# powerboard_v1.net
KiCad netlist of a schematic drawn in EAGLE
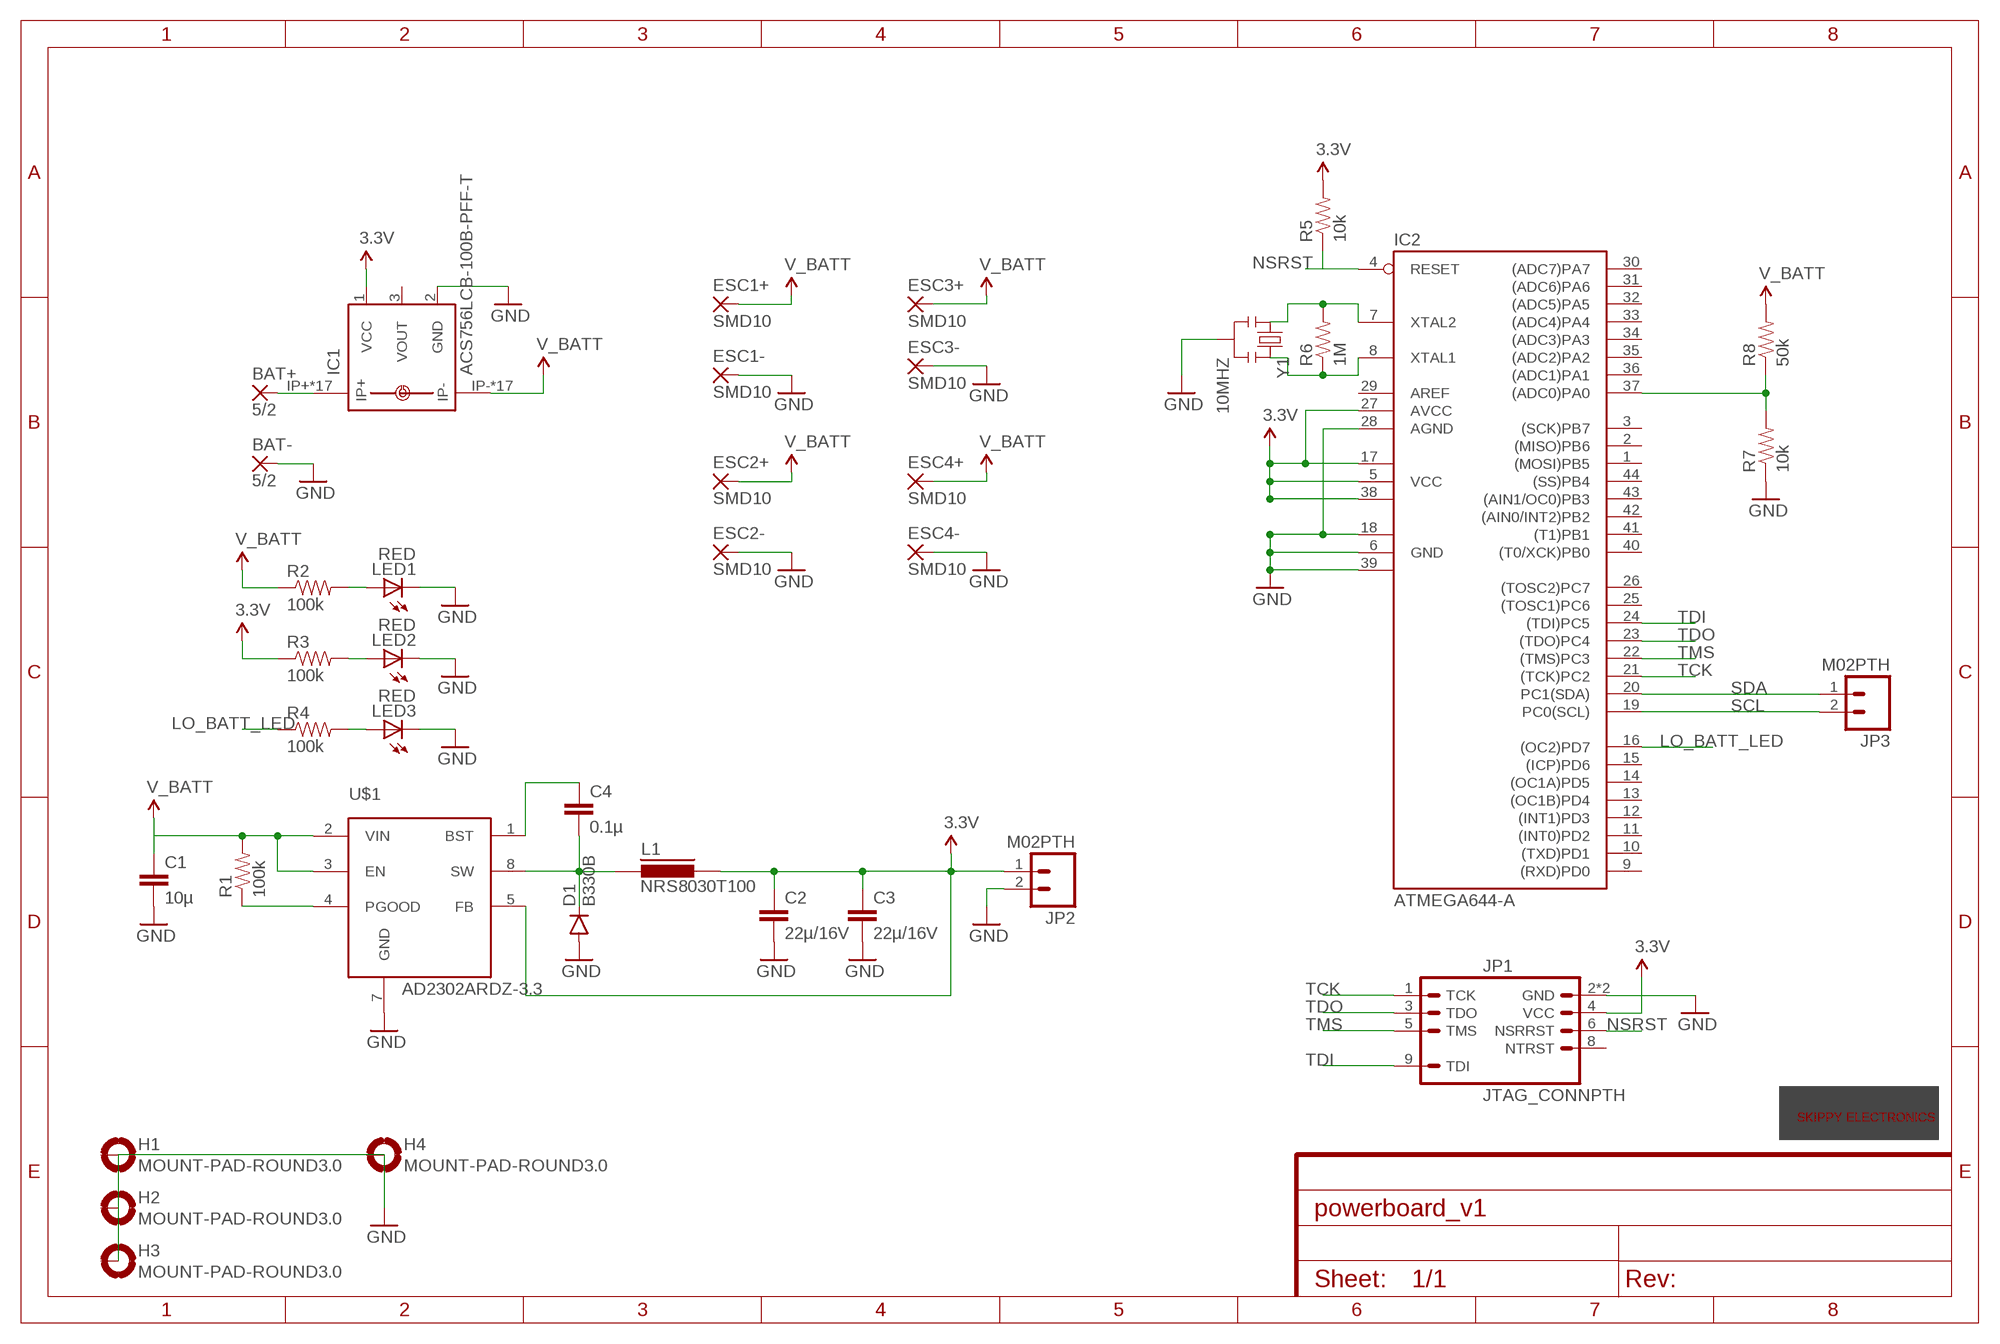
[diagram p0: schematic, sheet 1]

(export (version "E")
  (design (tool "Eeschema 10.0.6"))
  (components
    (comp (ref "BAT+")
      (value "5/2")
      (footprint "eagle-import:5_2")
      (libsource (lib "eagle-import") (part "5/2"))
    )
    (comp (ref "BAT-")
      (value "5/2")
      (footprint "eagle-import:5_2")
      (libsource (lib "eagle-import") (part "5/2"))
    )
    (comp (ref "C1")
      (value "10µ")
      (footprint "eagle-import:1206")
      (libsource (lib "eagle-import") (part "CAP1206"))
    )
    (comp (ref "C2")
      (value "22µ/16V")
      (footprint "eagle-import:1206")
      (libsource (lib "eagle-import") (part "CAP1206"))
    )
    (comp (ref "C3")
      (value "22µ/16V")
      (footprint "eagle-import:1206")
      (libsource (lib "eagle-import") (part "CAP1206"))
    )
    (comp (ref "C4")
      (value "0.1µ")
      (footprint "eagle-import:1206")
      (libsource (lib "eagle-import") (part "CAP1206"))
    )
    (comp (ref "D1")
      (value "B330B")
      (footprint "eagle-import:SMB-DIODE")
      (libsource (lib "eagle-import") (part "DIODESMB"))
    )
    (comp (ref "ESC1+")
      (value "SMD10")
      (footprint "eagle-import:SMD5.08-10.16")
      (libsource (lib "eagle-import") (part "SMD10"))
    )
    (comp (ref "ESC1-")
      (value "SMD10")
      (footprint "eagle-import:SMD5.08-10.16")
      (libsource (lib "eagle-import") (part "SMD10"))
    )
    (comp (ref "ESC2+")
      (value "SMD10")
      (footprint "eagle-import:SMD5.08-10.16")
      (libsource (lib "eagle-import") (part "SMD10"))
    )
    (comp (ref "ESC2-")
      (value "SMD10")
      (footprint "eagle-import:SMD5.08-10.16")
      (libsource (lib "eagle-import") (part "SMD10"))
    )
    (comp (ref "ESC3+")
      (value "SMD10")
      (footprint "eagle-import:SMD5.08-10.16")
      (libsource (lib "eagle-import") (part "SMD10"))
    )
    (comp (ref "ESC3-")
      (value "SMD10")
      (footprint "eagle-import:SMD5.08-10.16")
      (libsource (lib "eagle-import") (part "SMD10"))
    )
    (comp (ref "ESC4+")
      (value "SMD10")
      (footprint "eagle-import:SMD5.08-10.16")
      (libsource (lib "eagle-import") (part "SMD10"))
    )
    (comp (ref "ESC4-")
      (value "SMD10")
      (footprint "eagle-import:SMD5.08-10.16")
      (libsource (lib "eagle-import") (part "SMD10"))
    )
    (comp (ref "H1")
      (value "MOUNT-PAD-ROUND3.0")
      (footprint "eagle-import:3,0-PAD")
      (libsource (lib "eagle-import") (part "MOUNT-PAD-ROUND3.0"))
    )
    (comp (ref "H2")
      (value "MOUNT-PAD-ROUND3.0")
      (footprint "eagle-import:3,0-PAD")
      (libsource (lib "eagle-import") (part "MOUNT-PAD-ROUND3.0"))
    )
    (comp (ref "H3")
      (value "MOUNT-PAD-ROUND3.0")
      (footprint "eagle-import:3,0-PAD")
      (libsource (lib "eagle-import") (part "MOUNT-PAD-ROUND3.0"))
    )
    (comp (ref "H4")
      (value "MOUNT-PAD-ROUND3.0")
      (footprint "eagle-import:3,0-PAD")
      (libsource (lib "eagle-import") (part "MOUNT-PAD-ROUND3.0"))
    )
    (comp (ref "IC1")
      (value "ACS756LCB-100B-PFF-T")
      (footprint "eagle-import:CB-PFF")
      (fields (field (name "MPN") "ACS758LCB-100B-PFF-T"))
      (libsource (lib "eagle-import") (part "ACS756LCB-100B-PFF-T"))
    )
    (comp (ref "IC2")
      (value "ATMEGA644-A")
      (footprint "eagle-import:TQFP44")
      (libsource (lib "eagle-import") (part "ATMEGA644-A"))
    )
    (comp (ref "JP1")
      (value "JTAG_CONNPTH")
      (footprint "eagle-import:AVR_ICSP")
      (libsource (lib "eagle-import") (part "JTAG_CONNPTH"))
    )
    (comp (ref "JP2")
      (value "M02PTH")
      (footprint "eagle-import:1X02")
      (libsource (lib "eagle-import") (part "M02PTH"))
    )
    (comp (ref "JP3")
      (value "M02PTH")
      (footprint "eagle-import:1X02")
      (libsource (lib "eagle-import") (part "M02PTH"))
    )
    (comp (ref "L1")
      (value "NRS8030T100")
      (footprint "eagle-import:NRS8030")
      (libsource (lib "eagle-import") (part "NRS8030T100"))
    )
    (comp (ref "LED1")
      (value "RED")
      (footprint "eagle-import:LED_1206")
      (libsource (lib "eagle-import") (part "LED_E"))
    )
    (comp (ref "LED2")
      (value "RED")
      (footprint "eagle-import:LED_1206")
      (libsource (lib "eagle-import") (part "LED_E"))
    )
    (comp (ref "LED3")
      (value "RED")
      (footprint "eagle-import:LED_1206")
      (libsource (lib "eagle-import") (part "LED_E"))
    )
    (comp (ref "PLC1")
      (value "SKIPPY-PLC-10MMPLC")
      (footprint "eagle-import:SKIPPY-PLC-10MM")
      (libsource (lib "eagle-import") (part "SKIPPY-PLC-10MMPLC"))
    )
    (comp (ref "R1")
      (value "100k")
      (footprint "eagle-import:1206")
      (libsource (lib "eagle-import") (part "RESISTOR1206"))
    )
    (comp (ref "R2")
      (value "100k")
      (footprint "eagle-import:1206")
      (libsource (lib "eagle-import") (part "RESISTOR1206"))
    )
    (comp (ref "R3")
      (value "100k")
      (footprint "eagle-import:1206")
      (libsource (lib "eagle-import") (part "RESISTOR1206"))
    )
    (comp (ref "R4")
      (value "100k")
      (footprint "eagle-import:1206")
      (libsource (lib "eagle-import") (part "RESISTOR1206"))
    )
    (comp (ref "R5")
      (value "10k")
      (footprint "eagle-import:1206")
      (libsource (lib "eagle-import") (part "RESISTOR1206"))
    )
    (comp (ref "R6")
      (value "1M")
      (footprint "eagle-import:1206")
      (libsource (lib "eagle-import") (part "RESISTOR1206"))
    )
    (comp (ref "R7")
      (value "10k")
      (footprint "eagle-import:1206")
      (libsource (lib "eagle-import") (part "RESISTOR1206"))
    )
    (comp (ref "R8")
      (value "50k")
      (footprint "eagle-import:1206")
      (libsource (lib "eagle-import") (part "RESISTOR1206"))
    )
    (comp (ref "U$1")
      (value "AD2302ARDZ-3.3")
      (footprint "eagle-import:SO8")
      (libsource (lib "eagle-import") (part "AD2302ARDZ-3.3"))
    )
    (comp (ref "Y1")
      (value "10MHZ")
      (footprint "eagle-import:RESONATOR-SMD")
      (libsource (lib "eagle-import") (part "RESONATOR8MHZ"))
    )
  )
  (nets
    (net (code "1") (name "/LO_BATT_LED") (class "Default")
      (node (ref "IC2") (pin "16") (pinfunction "(OC2)PD7_16") (pintype "bidirectional"))
      (node (ref "R4") (pin "1") (pinfunction "1_1") (pintype "passive"))
    )
    (net (code "2") (name "/NSRST") (class "Default")
      (node (ref "IC2") (pin "4") (pinfunction "RESET_4") (pintype "input"))
      (node (ref "JP1") (pin "6") (pinfunction "NSRRST_6") (pintype "passive"))
      (node (ref "R5") (pin "1") (pinfunction "1_1") (pintype "passive"))
    )
    (net (code "3") (name "/SCL") (class "Default")
      (node (ref "IC2") (pin "19") (pinfunction "PC0(SCL)_19") (pintype "bidirectional"))
      (node (ref "JP3") (pin "2") (pinfunction "2_2") (pintype "passive"))
    )
    (net (code "4") (name "/SDA") (class "Default")
      (node (ref "IC2") (pin "20") (pinfunction "PC1(SDA)_20") (pintype "bidirectional"))
      (node (ref "JP3") (pin "1") (pinfunction "1_1") (pintype "passive"))
    )
    (net (code "5") (name "/TCK") (class "Default")
      (node (ref "IC2") (pin "21") (pinfunction "(TCK)PC2_21") (pintype "bidirectional"))
      (node (ref "JP1") (pin "1") (pinfunction "TCK_1") (pintype "passive"))
    )
    (net (code "6") (name "/TDI") (class "Default")
      (node (ref "IC2") (pin "24") (pinfunction "(TDI)PC5_24") (pintype "bidirectional"))
      (node (ref "JP1") (pin "9") (pinfunction "TDI_9") (pintype "passive"))
    )
    (net (code "7") (name "/TDO") (class "Default")
      (node (ref "IC2") (pin "23") (pinfunction "(TDO)PC4_23") (pintype "bidirectional"))
      (node (ref "JP1") (pin "3") (pinfunction "TDO_3") (pintype "passive"))
    )
    (net (code "8") (name "/TMS") (class "Default")
      (node (ref "IC2") (pin "22") (pinfunction "(TMS)PC3_22") (pintype "bidirectional"))
      (node (ref "JP1") (pin "5") (pinfunction "TMS_5") (pintype "passive"))
    )
    (net (code "9") (name "3.3V") (class "Default")
      (node (ref "C2") (pin "1") (pinfunction "1_1") (pintype "passive"))
      (node (ref "C3") (pin "1") (pinfunction "1_1") (pintype "passive"))
      (node (ref "IC1") (pin "1") (pinfunction "VCC_1") (pintype "power_in"))
      (node (ref "IC2") (pin "17") (pinfunction "VCC1_17") (pintype "power_in"))
      (node (ref "IC2") (pin "27") (pinfunction "AVCC_27") (pintype "power_in"))
      (node (ref "IC2") (pin "38") (pinfunction "VCC2_38") (pintype "power_in"))
      (node (ref "IC2") (pin "5") (pinfunction "VCC_5") (pintype "power_in"))
      (node (ref "JP1") (pin "4") (pinfunction "VCC_4") (pintype "passive"))
      (node (ref "JP2") (pin "1") (pinfunction "1_1") (pintype "passive"))
      (node (ref "L1") (pin "P$2") (pinfunction "2_P$2") (pintype "passive"))
      (node (ref "R3") (pin "1") (pinfunction "1_1") (pintype "passive"))
      (node (ref "R5") (pin "2") (pinfunction "2_2") (pintype "passive"))
      (node (ref "U$1") (pin "5") (pinfunction "FB_5") (pintype "input"))
    )
    (net (code "10") (name "GND") (class "Default")
      (node (ref "BAT-") (pin "P$1") (pinfunction "P_P$1") (pintype "passive"))
      (node (ref "C1") (pin "2") (pinfunction "2_2") (pintype "passive"))
      (node (ref "C2") (pin "2") (pinfunction "2_2") (pintype "passive"))
      (node (ref "C3") (pin "2") (pinfunction "2_2") (pintype "passive"))
      (node (ref "D1") (pin "A") (pinfunction "A_A") (pintype "passive"))
      (node (ref "ESC1-") (pin "P$1") (pinfunction "P_P$1") (pintype "passive"))
      (node (ref "ESC1-") (pin "P$2") (pinfunction "P_P$2") (pintype "passive"))
      (node (ref "ESC2-") (pin "P$1") (pinfunction "P_P$1") (pintype "passive"))
      (node (ref "ESC2-") (pin "P$2") (pinfunction "P_P$2") (pintype "passive"))
      (node (ref "ESC3-") (pin "P$1") (pinfunction "P_P$1") (pintype "passive"))
      (node (ref "ESC3-") (pin "P$2") (pinfunction "P_P$2") (pintype "passive"))
      (node (ref "ESC4-") (pin "P$1") (pinfunction "P_P$1") (pintype "passive"))
      (node (ref "ESC4-") (pin "P$2") (pinfunction "P_P$2") (pintype "passive"))
      (node (ref "IC1") (pin "2") (pinfunction "GND_2") (pintype "power_in"))
      (node (ref "IC2") (pin "18") (pinfunction "GND1_18") (pintype "power_in"))
      (node (ref "IC2") (pin "28") (pinfunction "AGND_28") (pintype "power_in"))
      (node (ref "IC2") (pin "39") (pinfunction "GND2_39") (pintype "power_in"))
      (node (ref "IC2") (pin "6") (pinfunction "GND_6") (pintype "power_in"))
      (node (ref "JP1") (pin "10") (pinfunction "GND_10") (pintype "power_in"))
      (node (ref "JP1") (pin "2") (pinfunction "GND_2") (pintype "power_in"))
      (node (ref "JP2") (pin "2") (pinfunction "2_2") (pintype "passive"))
      (node (ref "LED1") (pin "C") (pinfunction "C_C") (pintype "passive"))
      (node (ref "LED2") (pin "C") (pinfunction "C_C") (pintype "passive"))
      (node (ref "LED3") (pin "C") (pinfunction "C_C") (pintype "passive"))
      (node (ref "R7") (pin "1") (pinfunction "1_1") (pintype "passive"))
      (node (ref "U$1") (pin "7") (pinfunction "GND_7") (pintype "power_in"))
      (node (ref "Y1") (pin "2") (pinfunction "2_2") (pintype "passive"))
    )
    (net (code "11") (name "Net-(BAT+-P)") (class "Default")
      (node (ref "BAT+") (pin "P$1") (pinfunction "P_P$1") (pintype "passive"))
      (node (ref "IC1") (pin "IP+") (pinfunction "IP+_IP+") (pintype "passive"))
      (node (ref "IC1") (pin "IP+@10") (pinfunction "IP+_IP+@10") (pintype "passive"))
      (node (ref "IC1") (pin "IP+@11") (pinfunction "IP+_IP+@11") (pintype "passive"))
      (node (ref "IC1") (pin "IP+@12") (pinfunction "IP+_IP+@12") (pintype "passive"))
      (node (ref "IC1") (pin "IP+@13") (pinfunction "IP+_IP+@13") (pintype "passive"))
      (node (ref "IC1") (pin "IP+@14") (pinfunction "IP+_IP+@14") (pintype "passive"))
      (node (ref "IC1") (pin "IP+@15") (pinfunction "IP+_IP+@15") (pintype "passive"))
      (node (ref "IC1") (pin "IP+@16") (pinfunction "IP+_IP+@16") (pintype "passive"))
      (node (ref "IC1") (pin "IP+@17") (pinfunction "IP+_IP+@17") (pintype "passive"))
      (node (ref "IC1") (pin "IP+@2") (pinfunction "IP+_IP+@2") (pintype "passive"))
      (node (ref "IC1") (pin "IP+@3") (pinfunction "IP+_IP+@3") (pintype "passive"))
      (node (ref "IC1") (pin "IP+@4") (pinfunction "IP+_IP+@4") (pintype "passive"))
      (node (ref "IC1") (pin "IP+@5") (pinfunction "IP+_IP+@5") (pintype "passive"))
      (node (ref "IC1") (pin "IP+@6") (pinfunction "IP+_IP+@6") (pintype "passive"))
      (node (ref "IC1") (pin "IP+@7") (pinfunction "IP+_IP+@7") (pintype "passive"))
      (node (ref "IC1") (pin "IP+@8") (pinfunction "IP+_IP+@8") (pintype "passive"))
      (node (ref "IC1") (pin "IP+@9") (pinfunction "IP+_IP+@9") (pintype "passive"))
    )
    (net (code "12") (name "Net-(IC2-(ADC0)PA0)") (class "Default")
      (node (ref "IC2") (pin "37") (pinfunction "(ADC0)PA0_37") (pintype "bidirectional"))
      (node (ref "R7") (pin "2") (pinfunction "2_2") (pintype "passive"))
      (node (ref "R8") (pin "1") (pinfunction "1_1") (pintype "passive"))
    )
    (net (code "13") (name "Net-(IC2-XTAL1)") (class "Default")
      (node (ref "IC2") (pin "8") (pinfunction "XTAL1_8") (pintype "bidirectional"))
      (node (ref "R6") (pin "1") (pinfunction "1_1") (pintype "passive"))
      (node (ref "Y1") (pin "3") (pinfunction "3_3") (pintype "passive"))
    )
    (net (code "14") (name "Net-(IC2-XTAL2)") (class "Default")
      (node (ref "IC2") (pin "7") (pinfunction "XTAL2_7") (pintype "bidirectional"))
      (node (ref "R6") (pin "2") (pinfunction "2_2") (pintype "passive"))
      (node (ref "Y1") (pin "1") (pinfunction "1_1") (pintype "passive"))
    )
    (net (code "15") (name "Net-(L1-1)") (class "Default")
      (node (ref "C4") (pin "2") (pinfunction "2_2") (pintype "passive"))
      (node (ref "D1") (pin "C") (pinfunction "C_C") (pintype "passive"))
      (node (ref "L1") (pin "P$1") (pinfunction "1_P$1") (pintype "passive"))
      (node (ref "U$1") (pin "8") (pinfunction "SW_8") (pintype "power_in"))
    )
    (net (code "16") (name "Net-(LED1-PadA)") (class "Default")
      (node (ref "LED1") (pin "A") (pinfunction "A_A") (pintype "passive"))
      (node (ref "R2") (pin "2") (pinfunction "2_2") (pintype "passive"))
    )
    (net (code "17") (name "Net-(LED2-PadA)") (class "Default")
      (node (ref "LED2") (pin "A") (pinfunction "A_A") (pintype "passive"))
      (node (ref "R3") (pin "2") (pinfunction "2_2") (pintype "passive"))
    )
    (net (code "18") (name "Net-(LED3-PadA)") (class "Default")
      (node (ref "LED3") (pin "A") (pinfunction "A_A") (pintype "passive"))
      (node (ref "R4") (pin "2") (pinfunction "2_2") (pintype "passive"))
    )
    (net (code "19") (name "Net-(U$1-BST)") (class "Default")
      (node (ref "C4") (pin "1") (pinfunction "1_1") (pintype "passive"))
      (node (ref "U$1") (pin "1") (pinfunction "BST_1") (pintype "power_in"))
    )
    (net (code "20") (name "Net-(U$1-PGOOD)") (class "Default")
      (node (ref "R1") (pin "1") (pinfunction "1_1") (pintype "passive"))
      (node (ref "U$1") (pin "4") (pinfunction "PGOOD_4") (pintype "output"))
    )
    (net (code "21") (name "V_BATT") (class "Default")
      (node (ref "C1") (pin "1") (pinfunction "1_1") (pintype "passive"))
      (node (ref "ESC1+") (pin "P$1") (pinfunction "P_P$1") (pintype "passive"))
      (node (ref "ESC1+") (pin "P$2") (pinfunction "P_P$2") (pintype "passive"))
      (node (ref "ESC2+") (pin "P$1") (pinfunction "P_P$1") (pintype "passive"))
      (node (ref "ESC2+") (pin "P$2") (pinfunction "P_P$2") (pintype "passive"))
      (node (ref "ESC3+") (pin "P$1") (pinfunction "P_P$1") (pintype "passive"))
      (node (ref "ESC3+") (pin "P$2") (pinfunction "P_P$2") (pintype "passive"))
      (node (ref "ESC4+") (pin "P$1") (pinfunction "P_P$1") (pintype "passive"))
      (node (ref "ESC4+") (pin "P$2") (pinfunction "P_P$2") (pintype "passive"))
      (node (ref "IC1") (pin "IP-") (pinfunction "IP-_IP-") (pintype "passive"))
      (node (ref "IC1") (pin "IP-@10") (pinfunction "IP-_IP-@10") (pintype "passive"))
      (node (ref "IC1") (pin "IP-@11") (pinfunction "IP-_IP-@11") (pintype "passive"))
      (node (ref "IC1") (pin "IP-@12") (pinfunction "IP-_IP-@12") (pintype "passive"))
      (node (ref "IC1") (pin "IP-@13") (pinfunction "IP-_IP-@13") (pintype "passive"))
      (node (ref "IC1") (pin "IP-@14") (pinfunction "IP-_IP-@14") (pintype "passive"))
      (node (ref "IC1") (pin "IP-@15") (pinfunction "IP-_IP-@15") (pintype "passive"))
      (node (ref "IC1") (pin "IP-@16") (pinfunction "IP-_IP-@16") (pintype "passive"))
      (node (ref "IC1") (pin "IP-@17") (pinfunction "IP-_IP-@17") (pintype "passive"))
      (node (ref "IC1") (pin "IP-@2") (pinfunction "IP-_IP-@2") (pintype "passive"))
      (node (ref "IC1") (pin "IP-@3") (pinfunction "IP-_IP-@3") (pintype "passive"))
      (node (ref "IC1") (pin "IP-@4") (pinfunction "IP-_IP-@4") (pintype "passive"))
      (node (ref "IC1") (pin "IP-@5") (pinfunction "IP-_IP-@5") (pintype "passive"))
      (node (ref "IC1") (pin "IP-@6") (pinfunction "IP-_IP-@6") (pintype "passive"))
      (node (ref "IC1") (pin "IP-@7") (pinfunction "IP-_IP-@7") (pintype "passive"))
      (node (ref "IC1") (pin "IP-@8") (pinfunction "IP-_IP-@8") (pintype "passive"))
      (node (ref "IC1") (pin "IP-@9") (pinfunction "IP-_IP-@9") (pintype "passive"))
      (node (ref "R1") (pin "2") (pinfunction "2_2") (pintype "passive"))
      (node (ref "R2") (pin "1") (pinfunction "1_1") (pintype "passive"))
      (node (ref "R8") (pin "2") (pinfunction "2_2") (pintype "passive"))
      (node (ref "U$1") (pin "2") (pinfunction "VIN_2") (pintype "power_in"))
      (node (ref "U$1") (pin "3") (pinfunction "EN_3") (pintype "input"))
    )
    (net (code "22") (name "unconnected-(H1-MOUNT-PadB3,0)") (class "Default")
      (node (ref "H1") (pin "B3,0") (pinfunction "MOUNT_B3,0") (pintype "passive"))
    )
    (net (code "23") (name "unconnected-(H2-MOUNT-PadB3,0)") (class "Default")
      (node (ref "H2") (pin "B3,0") (pinfunction "MOUNT_B3,0") (pintype "passive"))
    )
    (net (code "24") (name "unconnected-(H3-MOUNT-PadB3,0)") (class "Default")
      (node (ref "H3") (pin "B3,0") (pinfunction "MOUNT_B3,0") (pintype "passive"))
    )
    (net (code "25") (name "unconnected-(H4-MOUNT-PadB3,0)") (class "Default")
      (node (ref "H4") (pin "B3,0") (pinfunction "MOUNT_B3,0") (pintype "passive"))
    )
    (net (code "26") (name "unconnected-(IC1-VOUT-Pad3)") (class "Default")
      (node (ref "IC1") (pin "3") (pinfunction "VOUT_3") (pintype "output"))
    )
    (net (code "27") (name "unconnected-(IC2-(ADC1)PA1-Pad36)") (class "Default")
      (node (ref "IC2") (pin "36") (pinfunction "(ADC1)PA1_36") (pintype "bidirectional"))
    )
    (net (code "28") (name "unconnected-(IC2-(ADC2)PA2-Pad35)") (class "Default")
      (node (ref "IC2") (pin "35") (pinfunction "(ADC2)PA2_35") (pintype "bidirectional"))
    )
    (net (code "29") (name "unconnected-(IC2-(ADC3)PA3-Pad34)") (class "Default")
      (node (ref "IC2") (pin "34") (pinfunction "(ADC3)PA3_34") (pintype "bidirectional"))
    )
    (net (code "30") (name "unconnected-(IC2-(ADC4)PA4-Pad33)") (class "Default")
      (node (ref "IC2") (pin "33") (pinfunction "(ADC4)PA4_33") (pintype "bidirectional"))
    )
    (net (code "31") (name "unconnected-(IC2-(ADC5)PA5-Pad32)") (class "Default")
      (node (ref "IC2") (pin "32") (pinfunction "(ADC5)PA5_32") (pintype "bidirectional"))
    )
    (net (code "32") (name "unconnected-(IC2-(ADC6)PA6-Pad31)") (class "Default")
      (node (ref "IC2") (pin "31") (pinfunction "(ADC6)PA6_31") (pintype "bidirectional"))
    )
    (net (code "33") (name "unconnected-(IC2-(ADC7)PA7-Pad30)") (class "Default")
      (node (ref "IC2") (pin "30") (pinfunction "(ADC7)PA7_30") (pintype "bidirectional"))
    )
    (net (code "34") (name "unconnected-(IC2-(AIN0{slash}INT2)PB2-Pad42)") (class "Default")
      (node (ref "IC2") (pin "42") (pinfunction "(AIN0/INT2)PB2_42") (pintype "bidirectional"))
    )
    (net (code "35") (name "unconnected-(IC2-(AIN1{slash}OC0)PB3-Pad43)") (class "Default")
      (node (ref "IC2") (pin "43") (pinfunction "(AIN1/OC0)PB3_43") (pintype "bidirectional"))
    )
    (net (code "36") (name "unconnected-(IC2-(ICP)PD6-Pad15)") (class "Default")
      (node (ref "IC2") (pin "15") (pinfunction "(ICP)PD6_15") (pintype "bidirectional"))
    )
    (net (code "37") (name "unconnected-(IC2-(INT0)PD2-Pad11)") (class "Default")
      (node (ref "IC2") (pin "11") (pinfunction "(INT0)PD2_11") (pintype "bidirectional"))
    )
    (net (code "38") (name "unconnected-(IC2-(INT1)PD3-Pad12)") (class "Default")
      (node (ref "IC2") (pin "12") (pinfunction "(INT1)PD3_12") (pintype "bidirectional"))
    )
    (net (code "39") (name "unconnected-(IC2-(MISO)PB6-Pad2)") (class "Default")
      (node (ref "IC2") (pin "2") (pinfunction "(MISO)PB6_2") (pintype "bidirectional"))
    )
    (net (code "40") (name "unconnected-(IC2-(MOSI)PB5-Pad1)") (class "Default")
      (node (ref "IC2") (pin "1") (pinfunction "(MOSI)PB5_1") (pintype "bidirectional"))
    )
    (net (code "41") (name "unconnected-(IC2-(OC1A)PD5-Pad14)") (class "Default")
      (node (ref "IC2") (pin "14") (pinfunction "(OC1A)PD5_14") (pintype "bidirectional"))
    )
    (net (code "42") (name "unconnected-(IC2-(OC1B)PD4-Pad13)") (class "Default")
      (node (ref "IC2") (pin "13") (pinfunction "(OC1B)PD4_13") (pintype "bidirectional"))
    )
    (net (code "43") (name "unconnected-(IC2-(RXD)PD0-Pad9)") (class "Default")
      (node (ref "IC2") (pin "9") (pinfunction "(RXD)PD0_9") (pintype "bidirectional"))
    )
    (net (code "44") (name "unconnected-(IC2-(SCK)PB7-Pad3)") (class "Default")
      (node (ref "IC2") (pin "3") (pinfunction "(SCK)PB7_3") (pintype "bidirectional"))
    )
    (net (code "45") (name "unconnected-(IC2-(SS)PB4-Pad44)") (class "Default")
      (node (ref "IC2") (pin "44") (pinfunction "(SS)PB4_44") (pintype "bidirectional"))
    )
    (net (code "46") (name "unconnected-(IC2-(T0{slash}XCK)PB0-Pad40)") (class "Default")
      (node (ref "IC2") (pin "40") (pinfunction "(T0/XCK)PB0_40") (pintype "bidirectional"))
    )
    (net (code "47") (name "unconnected-(IC2-(T1)PB1-Pad41)") (class "Default")
      (node (ref "IC2") (pin "41") (pinfunction "(T1)PB1_41") (pintype "bidirectional"))
    )
    (net (code "48") (name "unconnected-(IC2-(TOSC1)PC6-Pad25)") (class "Default")
      (node (ref "IC2") (pin "25") (pinfunction "(TOSC1)PC6_25") (pintype "bidirectional"))
    )
    (net (code "49") (name "unconnected-(IC2-(TOSC2)PC7-Pad26)") (class "Default")
      (node (ref "IC2") (pin "26") (pinfunction "(TOSC2)PC7_26") (pintype "bidirectional"))
    )
    (net (code "50") (name "unconnected-(IC2-(TXD)PD1-Pad10)") (class "Default")
      (node (ref "IC2") (pin "10") (pinfunction "(TXD)PD1_10") (pintype "bidirectional"))
    )
    (net (code "51") (name "unconnected-(IC2-AREF-Pad29)") (class "Default")
      (node (ref "IC2") (pin "29") (pinfunction "AREF_29") (pintype "passive"))
    )
    (net (code "52") (name "unconnected-(JP1-NTRST-Pad8)") (class "Default")
      (node (ref "JP1") (pin "8") (pinfunction "NTRST_8") (pintype "passive"))
    )
  )
)
